# design.net
KiCad netlist of a schematic drawn in EasyEDA Pro
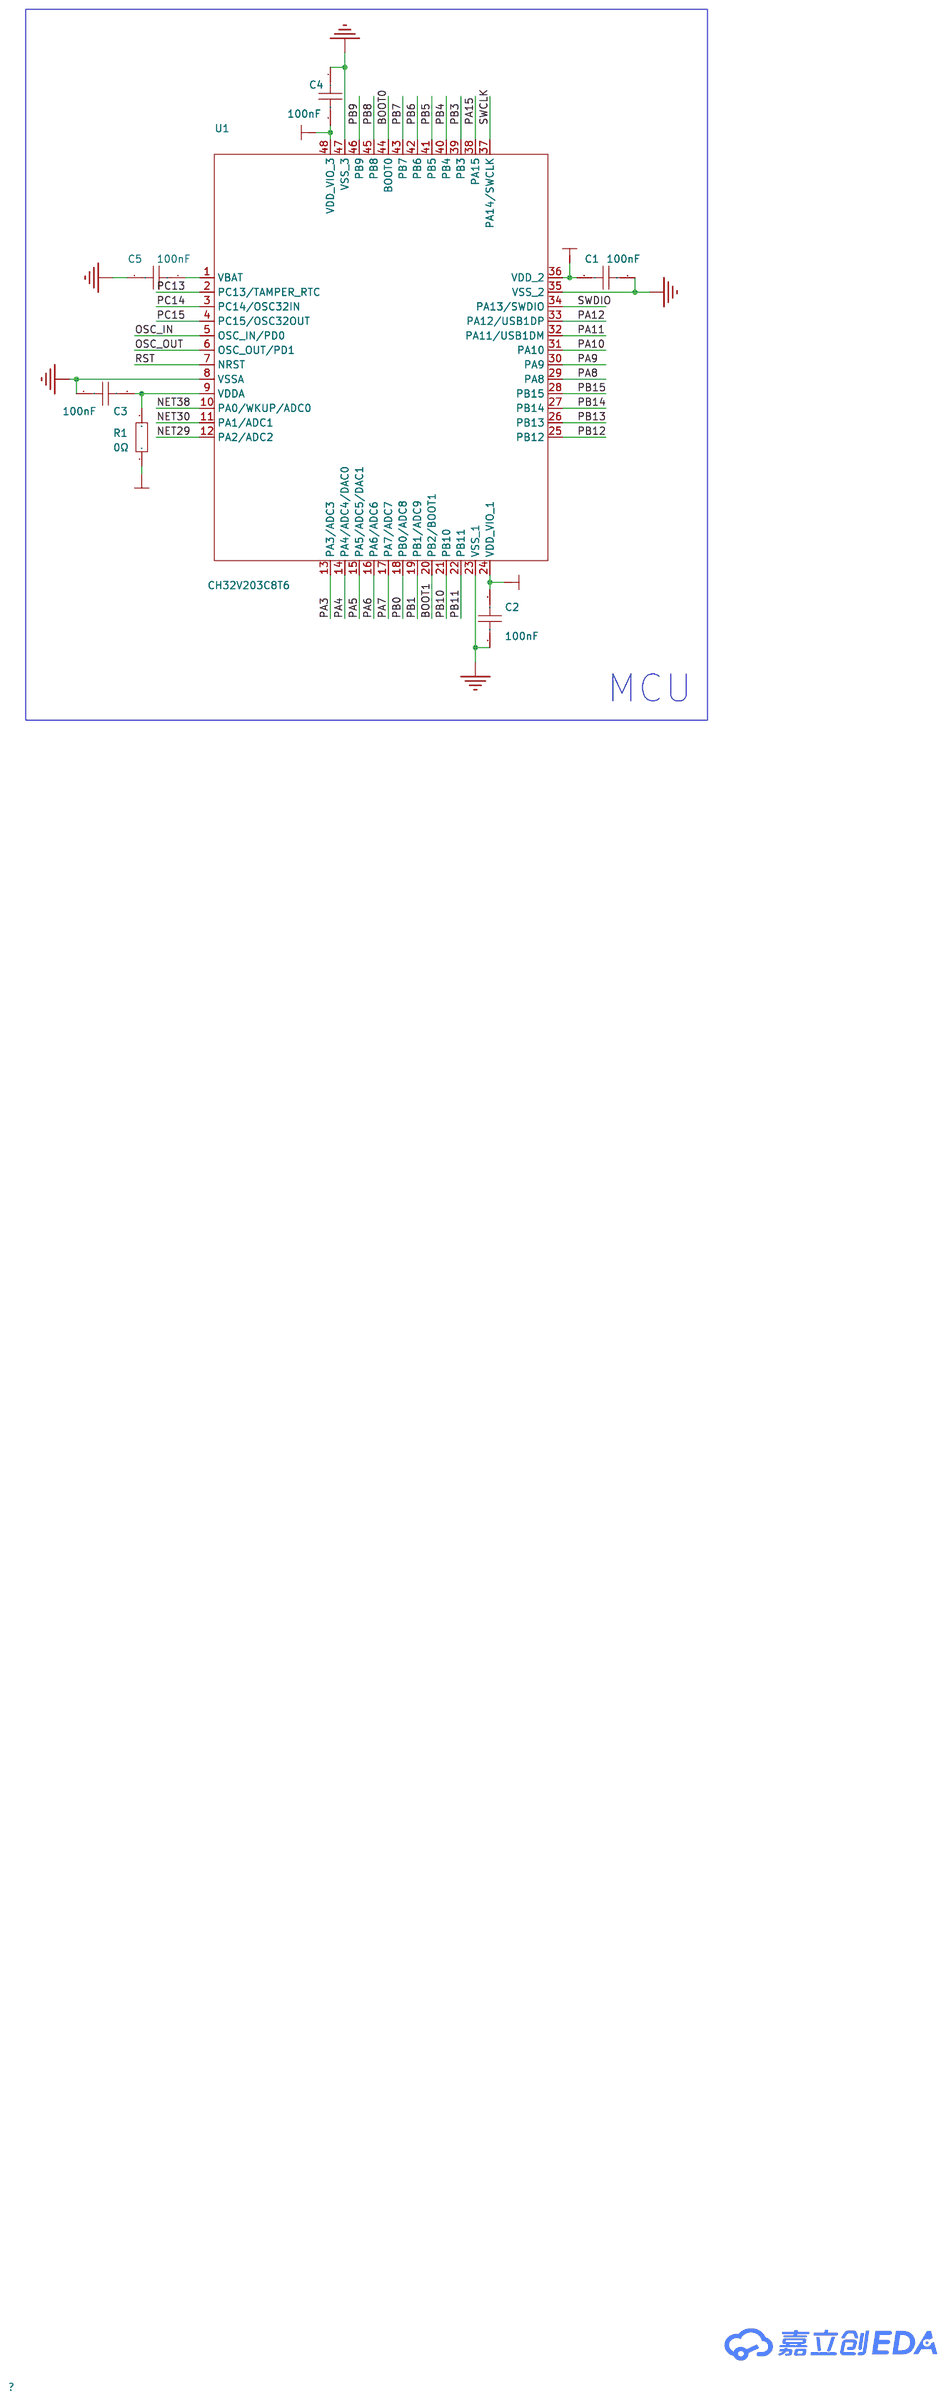
[diagram p0: schematic sheet]

(export (version "E")
  (design (tool "Eeschema 10.0.6"))
  (components
    (comp (ref "C1")
      (value "100nF")
      (footprint "easyedapro:C0603")
      (description "容值:100nF;精度:±10%;额定电压:50V;温度系数:X7R;")
      (fields
        (field (name "Manufacturer Part") "CGA0603X7R104K500JT")
        (field (name "Manufacturer") "HRE(芯声)")
      )
      (libsource (lib "easyedapro") (part "CGA0603X7R104K500JT"))
    )
    (comp (ref "C2")
      (value "100nF")
      (footprint "easyedapro:C0603")
      (description "容值:100nF;精度:±10%;额定电压:50V;温度系数:X7R;")
      (fields
        (field (name "Manufacturer Part") "CGA0603X7R104K500JT")
        (field (name "Manufacturer") "HRE(芯声)")
      )
      (libsource (lib "easyedapro") (part "CGA0603X7R104K500JT"))
    )
    (comp (ref "C3")
      (value "100nF")
      (footprint "easyedapro:C0603")
      (description "容值:100nF;精度:±10%;额定电压:50V;温度系数:X7R;")
      (fields
        (field (name "Manufacturer Part") "CGA0603X7R104K500JT")
        (field (name "Manufacturer") "HRE(芯声)")
      )
      (libsource (lib "easyedapro") (part "CGA0603X7R104K500JT"))
    )
    (comp (ref "C4")
      (value "100nF")
      (footprint "easyedapro:C0603")
      (description "容值:100nF;精度:±10%;额定电压:50V;温度系数:X7R;")
      (fields
        (field (name "Manufacturer Part") "CGA0603X7R104K500JT")
        (field (name "Manufacturer") "HRE(芯声)")
      )
      (libsource (lib "easyedapro") (part "CGA0603X7R104K500JT"))
    )
    (comp (ref "C5")
      (value "100nF")
      (footprint "easyedapro:C0603")
      (description "容值:100nF;精度:±10%;额定电压:50V;温度系数:X7R;")
      (fields
        (field (name "Manufacturer Part") "CGA0603X7R104K500JT")
        (field (name "Manufacturer") "HRE(芯声)")
      )
      (libsource (lib "easyedapro") (part "CGA0603X7R104K500JT"))
    )
    (comp (ref "R1")
      (value "0Ω")
      (footprint "easyedapro:R0603")
      (description "电阻类型:厚膜电阻;阻值:0Ω;精度:±1%;功率:100mW;工作电压:75V;温度系数:-;")
      (fields
        (field (name "Manufacturer Part") "0603WAF0000T5E")
        (field (name "Manufacturer") "UNI-ROYAL(厚声)")
      )
      (libsource (lib "easyedapro") (part "0603WAF0000T5E"))
    )
    (comp (ref "U1")
      (value "CH32V203C8T6")
      (footprint "easyedapro:LQFP-48_L7.0-W7.0-P0.50-LS9.0-BL")
      (description "CPU内核:RISC-V;程序存储容量:64KB;RAM总容量:20KB;GPIO端口数量:-;工作电压范围:-;CPU最大主频:144MHz;程序存储器类型:FLASH;")
      (fields (field (name "Manufacturer") "WCH(南京沁恒)"))
      (libsource (lib "easyedapro") (part "CH32V203C8T6"))
    )
  )
  (nets
    (net (code "1") (name "/BOOT0") (class "Default")
      (node (ref "U1") (pin "44") (pinfunction "BOOT0_44") (pintype "unspecified"))
    )
    (net (code "2") (name "/BOOT1") (class "Default")
      (node (ref "U1") (pin "20") (pinfunction "PB2/BOOT1_20") (pintype "unspecified"))
    )
    (net (code "3") (name "/NET29") (class "Default")
      (node (ref "U1") (pin "12") (pinfunction "PA2/ADC2_12") (pintype "unspecified"))
    )
    (net (code "4") (name "/NET30") (class "Default")
      (node (ref "U1") (pin "11") (pinfunction "PA1/ADC1_11") (pintype "unspecified"))
    )
    (net (code "5") (name "/NET38") (class "Default")
      (node (ref "U1") (pin "10") (pinfunction "PA0/WKUP/ADC0_10") (pintype "unspecified"))
    )
    (net (code "6") (name "/OSC_IN") (class "Default")
      (node (ref "U1") (pin "5") (pinfunction "OSC_IN/PD0_5") (pintype "unspecified"))
    )
    (net (code "7") (name "/OSC_OUT") (class "Default")
      (node (ref "U1") (pin "6") (pinfunction "OSC_OUT/PD1_6") (pintype "unspecified"))
    )
    (net (code "8") (name "/PA3") (class "Default")
      (node (ref "U1") (pin "13") (pinfunction "PA3/ADC3_13") (pintype "unspecified"))
    )
    (net (code "9") (name "/PA4") (class "Default")
      (node (ref "U1") (pin "14") (pinfunction "PA4/ADC4/DAC0_14") (pintype "unspecified"))
    )
    (net (code "10") (name "/PA5") (class "Default")
      (node (ref "U1") (pin "15") (pinfunction "PA5/ADC5/DAC1_15") (pintype "unspecified"))
    )
    (net (code "11") (name "/PA6") (class "Default")
      (node (ref "U1") (pin "16") (pinfunction "PA6/ADC6_16") (pintype "unspecified"))
    )
    (net (code "12") (name "/PA7") (class "Default")
      (node (ref "U1") (pin "17") (pinfunction "PA7/ADC7_17") (pintype "unspecified"))
    )
    (net (code "13") (name "/PA8") (class "Default")
      (node (ref "U1") (pin "29") (pinfunction "PA8_29") (pintype "unspecified"))
    )
    (net (code "14") (name "/PA9") (class "Default")
      (node (ref "U1") (pin "30") (pinfunction "PA9_30") (pintype "unspecified"))
    )
    (net (code "15") (name "/PA10") (class "Default")
      (node (ref "U1") (pin "31") (pinfunction "PA10_31") (pintype "unspecified"))
    )
    (net (code "16") (name "/PA11") (class "Default")
      (node (ref "U1") (pin "32") (pinfunction "PA11/USB1DM_32") (pintype "unspecified"))
    )
    (net (code "17") (name "/PA12") (class "Default")
      (node (ref "U1") (pin "33") (pinfunction "PA12/USB1DP_33") (pintype "unspecified"))
    )
    (net (code "18") (name "/PA15") (class "Default")
      (node (ref "U1") (pin "38") (pinfunction "PA15_38") (pintype "unspecified"))
    )
    (net (code "19") (name "/PB0") (class "Default")
      (node (ref "U1") (pin "18") (pinfunction "PB0/ADC8_18") (pintype "unspecified"))
    )
    (net (code "20") (name "/PB1") (class "Default")
      (node (ref "U1") (pin "19") (pinfunction "PB1/ADC9_19") (pintype "unspecified"))
    )
    (net (code "21") (name "/PB3") (class "Default")
      (node (ref "U1") (pin "39") (pinfunction "PB3_39") (pintype "unspecified"))
    )
    (net (code "22") (name "/PB4") (class "Default")
      (node (ref "U1") (pin "40") (pinfunction "PB4_40") (pintype "unspecified"))
    )
    (net (code "23") (name "/PB5") (class "Default")
      (node (ref "U1") (pin "41") (pinfunction "PB5_41") (pintype "unspecified"))
    )
    (net (code "24") (name "/PB6") (class "Default")
      (node (ref "U1") (pin "42") (pinfunction "PB6_42") (pintype "unspecified"))
    )
    (net (code "25") (name "/PB7") (class "Default")
      (node (ref "U1") (pin "43") (pinfunction "PB7_43") (pintype "unspecified"))
    )
    (net (code "26") (name "/PB8") (class "Default")
      (node (ref "U1") (pin "45") (pinfunction "PB8_45") (pintype "unspecified"))
    )
    (net (code "27") (name "/PB9") (class "Default")
      (node (ref "U1") (pin "46") (pinfunction "PB9_46") (pintype "unspecified"))
    )
    (net (code "28") (name "/PB10") (class "Default")
      (node (ref "U1") (pin "21") (pinfunction "PB10_21") (pintype "unspecified"))
    )
    (net (code "29") (name "/PB11") (class "Default")
      (node (ref "U1") (pin "22") (pinfunction "PB11_22") (pintype "unspecified"))
    )
    (net (code "30") (name "/PB12") (class "Default")
      (node (ref "U1") (pin "25") (pinfunction "PB12_25") (pintype "unspecified"))
    )
    (net (code "31") (name "/PB13") (class "Default")
      (node (ref "U1") (pin "26") (pinfunction "PB13_26") (pintype "unspecified"))
    )
    (net (code "32") (name "/PB14") (class "Default")
      (node (ref "U1") (pin "27") (pinfunction "PB14_27") (pintype "unspecified"))
    )
    (net (code "33") (name "/PB15") (class "Default")
      (node (ref "U1") (pin "28") (pinfunction "PB15_28") (pintype "unspecified"))
    )
    (net (code "34") (name "/PC13") (class "Default")
      (node (ref "U1") (pin "2") (pinfunction "PC13/TAMPER_RTC_2") (pintype "unspecified"))
    )
    (net (code "35") (name "/PC14") (class "Default")
      (node (ref "U1") (pin "3") (pinfunction "PC14/OSC32IN_3") (pintype "unspecified"))
    )
    (net (code "36") (name "/PC15") (class "Default")
      (node (ref "U1") (pin "4") (pinfunction "PC15/OSC32OUT_4") (pintype "unspecified"))
    )
    (net (code "37") (name "/RST") (class "Default")
      (node (ref "U1") (pin "7") (pinfunction "NRST_7") (pintype "unspecified"))
    )
    (net (code "38") (name "/SWCLK") (class "Default")
      (node (ref "U1") (pin "37") (pinfunction "PA14/SWCLK_37") (pintype "unspecified"))
    )
    (net (code "39") (name "/SWDIO") (class "Default")
      (node (ref "U1") (pin "34") (pinfunction "PA13/SWDIO_34") (pintype "unspecified"))
    )
    (net (code "40") (name "3.3V") (class "Default")
      (node (ref "C1") (pin "1") (pinfunction "1_1") (pintype "unspecified"))
      (node (ref "C2") (pin "2") (pinfunction "2_2") (pintype "unspecified"))
      (node (ref "C4") (pin "2") (pinfunction "2_2") (pintype "unspecified"))
      (node (ref "R1") (pin "1") (pinfunction "1_1") (pintype "input"))
      (node (ref "U1") (pin "24") (pinfunction "VDD_VIO_1_24") (pintype "unspecified"))
      (node (ref "U1") (pin "36") (pinfunction "VDD_2_36") (pintype "unspecified"))
      (node (ref "U1") (pin "48") (pinfunction "VDD_VIO_3_48") (pintype "unspecified"))
    )
    (net (code "41") (name "GND") (class "Default")
      (node (ref "C1") (pin "2") (pinfunction "2_2") (pintype "unspecified"))
      (node (ref "C2") (pin "1") (pinfunction "1_1") (pintype "unspecified"))
      (node (ref "C3") (pin "2") (pinfunction "2_2") (pintype "unspecified"))
      (node (ref "C4") (pin "1") (pinfunction "1_1") (pintype "unspecified"))
      (node (ref "C5") (pin "2") (pinfunction "2_2") (pintype "unspecified"))
      (node (ref "U1") (pin "23") (pinfunction "VSS_1_23") (pintype "unspecified"))
      (node (ref "U1") (pin "35") (pinfunction "VSS_2_35") (pintype "unspecified"))
      (node (ref "U1") (pin "47") (pinfunction "VSS_3_47") (pintype "unspecified"))
      (node (ref "U1") (pin "8") (pinfunction "VSSA_8") (pintype "unspecified"))
    )
    (net (code "42") (name "Net-(U1-VBAT)") (class "Default")
      (node (ref "C5") (pin "1") (pinfunction "1_1") (pintype "unspecified"))
      (node (ref "U1") (pin "1") (pinfunction "VBAT_1") (pintype "unspecified"))
    )
    (net (code "43") (name "Net-(U1-VDDA)") (class "Default")
      (node (ref "C3") (pin "1") (pinfunction "1_1") (pintype "unspecified"))
      (node (ref "R1") (pin "2") (pinfunction "2_2") (pintype "input"))
      (node (ref "U1") (pin "9") (pinfunction "VDDA_9") (pintype "unspecified"))
    )
  )
)
